# Counter_PickUp_v2.net
KiCad netlist of a schematic drawn in Altium Designer
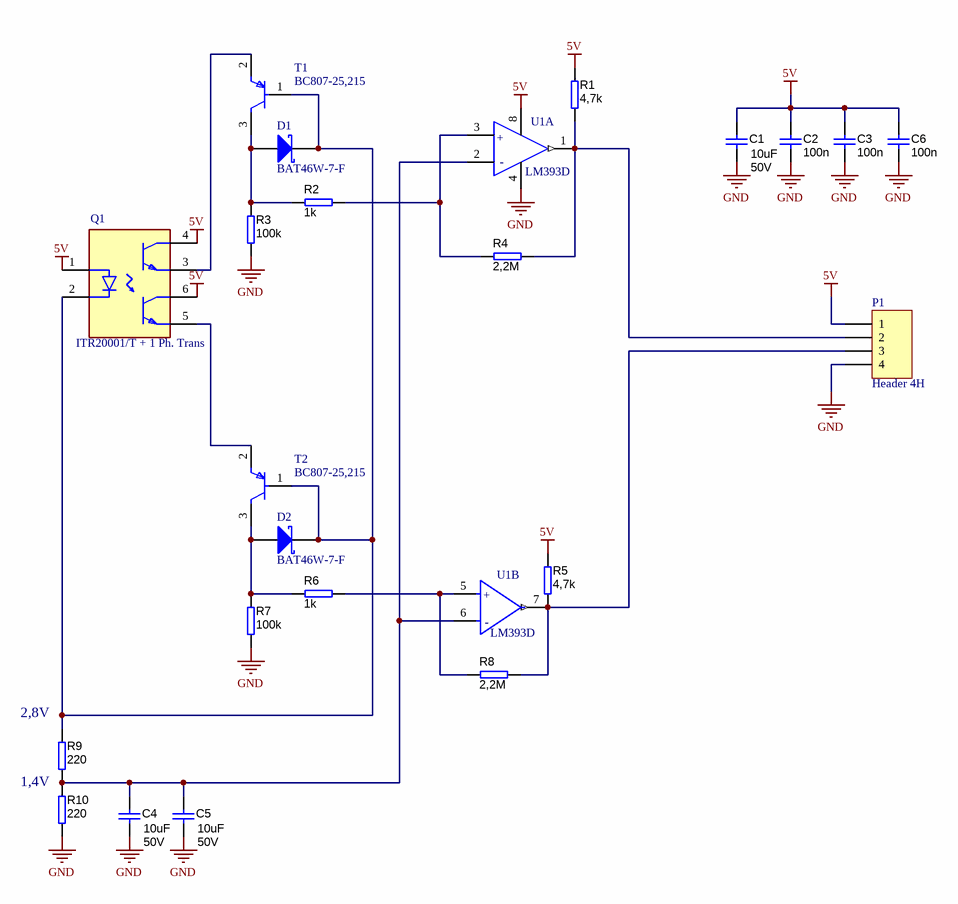
[diagram p0: Counter_PickUp_v2.SchDoc]

(export (version "E")
  (design (tool "Eeschema 10.0.6"))
  (components
    (comp (ref "C1")
      (value "10uF")
      (footprint "1206_180")
      (description "CAP, CERM, NP0, 1206")
      (fields (field (name "VALUE1") "50V"))
      (libsource (lib "Const_Cur_Source") (part "C1206"))
    )
    (comp (ref "C2")
      (value "100n")
      (footprint "0805_HV")
      (description "CAP, CERM, +/- 10%, X7S,  0805")
      (libsource (lib "Const_Cur_Source") (part "C0805"))
    )
    (comp (ref "C3")
      (value "100n")
      (footprint "0805_HV")
      (description "CAP, CERM, +/- 10%, X7S,  0805")
      (libsource (lib "Const_Cur_Source") (part "C0805"))
    )
    (comp (ref "C4")
      (value "10uF")
      (footprint "1206_180")
      (description "CAP, CERM, NP0, 1206")
      (fields (field (name "VALUE1") "50V"))
      (libsource (lib "Const_Cur_Source") (part "C1206"))
    )
    (comp (ref "C5")
      (value "10uF")
      (footprint "1206_180")
      (description "CAP, CERM, NP0, 1206")
      (fields (field (name "VALUE1") "50V"))
      (libsource (lib "Const_Cur_Source") (part "C1206"))
    )
    (comp (ref "C6")
      (value "100n")
      (footprint "0805_HV")
      (description "CAP, CERM, +/- 10%, X7S,  0805")
      (libsource (lib "Const_Cur_Source") (part "C0805"))
    )
    (comp (ref "D1")
      (value "BAT46W-7-F")
      (footprint "SOD-123-2_V")
      (description "Surface Mount Schottky Barrier Diode, 100 V, -55 to 125 degC, 2-Pin SOD123, RoHS, Tape and Reel")
      (fields (field (name "MANUFACTURER") "Diodes Inc"))
      (libsource (lib "Const_Cur_Source") (part "BAT46W-7-F"))
    )
    (comp (ref "D2")
      (value "BAT46W-7-F")
      (footprint "SOD-123-2_V")
      (description "Surface Mount Schottky Barrier Diode, 100 V, -55 to 125 degC, 2-Pin SOD123, RoHS, Tape and Reel")
      (fields (field (name "MANUFACTURER") "Diodes Inc"))
      (libsource (lib "Const_Cur_Source") (part "BAT46W-7-F"))
    )
    (comp (ref "P1")
      (value "Header 4H")
      (footprint "HDR1X4H")
      (description "Header, 4-Pin, Right Angle")
      (fields (field (name "PUBLISHER") "Altium Limited"))
      (libsource (lib "Miscellaneous Connectors") (part "Header 4H"))
    )
    (comp (ref "Q1")
      (value "Photo_T")
      (footprint "Photo_T")
      (libsource (lib "Const_Cur_Source") (part "Photo_T"))
    )
    (comp (ref "R1")
      (value "4,7k")
      (footprint "0805_HV")
      (description "RES, 1%, 0.1 W, 0805")
      (libsource (lib "Const_Cur_Source") (part "R0805"))
    )
    (comp (ref "R2")
      (value "1k")
      (footprint "0805_HV")
      (description "RES, 1%, 0.1 W, 0805")
      (libsource (lib "Const_Cur_Source") (part "R0805"))
    )
    (comp (ref "R3")
      (value "100k")
      (footprint "0805_HV")
      (description "RES, 1%, 0.1 W, 0805")
      (libsource (lib "Const_Cur_Source") (part "R0805"))
    )
    (comp (ref "R4")
      (value "2,2M")
      (footprint "0805_HV")
      (description "RES, 1%, 0.1 W, 0805")
      (libsource (lib "Const_Cur_Source") (part "R0805"))
    )
    (comp (ref "R5")
      (value "4,7k")
      (footprint "0805_HV")
      (description "RES, 1%, 0.1 W, 0805")
      (libsource (lib "Const_Cur_Source") (part "R0805"))
    )
    (comp (ref "R6")
      (value "1k")
      (footprint "0805_HV")
      (description "RES, 1%, 0.1 W, 0805")
      (libsource (lib "Const_Cur_Source") (part "R0805"))
    )
    (comp (ref "R7")
      (value "100k")
      (footprint "0805_HV")
      (description "RES, 1%, 0.1 W, 0805")
      (libsource (lib "Const_Cur_Source") (part "R0805"))
    )
    (comp (ref "R8")
      (value "2,2M")
      (footprint "0805_HV")
      (description "RES, 1%, 0.1 W, 0805")
      (libsource (lib "Const_Cur_Source") (part "R0805"))
    )
    (comp (ref "R9")
      (value "220")
      (footprint "0805_HV")
      (description "RES, 1%, 0.1 W, 0805")
      (libsource (lib "Const_Cur_Source") (part "R0805"))
    )
    (comp (ref "R10")
      (value "220")
      (footprint "0805_HV")
      (description "RES, 1%, 0.1 W, 0805")
      (libsource (lib "Const_Cur_Source") (part "R0805"))
    )
    (comp (ref "T1")
      (value "BC807-25,215")
      (footprint "SOT23_0")
      (libsource (lib "Const_Cur_Source") (part "BC807-25,215"))
    )
    (comp (ref "T2")
      (value "BC807-25,215")
      (footprint "SOT23_0")
      (libsource (lib "Const_Cur_Source") (part "BC807-25,215"))
    )
    (comp (ref "U1")
      (value "LM393D")
      (footprint "SO8_IPC_A")
      (libsource (lib "Const_Cur_Source") (part "LM393D"))
    )
  )
  (nets
    (net (code "1") (name "5V") (class "Default")
      (node (ref "C1") (pin "1") (pinfunction "1_1") (pintype "passive"))
      (node (ref "C2") (pin "2") (pinfunction "2_2") (pintype "passive"))
      (node (ref "C3") (pin "2") (pinfunction "2_2") (pintype "passive"))
      (node (ref "C6") (pin "2") (pinfunction "2_2") (pintype "passive"))
      (node (ref "P1") (pin "1") (pinfunction "1_1") (pintype "passive"))
      (node (ref "Q1") (pin "1") (pinfunction "1_ANODE_1") (pintype "passive"))
      (node (ref "Q1") (pin "4") (pinfunction "C_4") (pintype "passive"))
      (node (ref "Q1") (pin "6") (pinfunction "C_6") (pintype "passive"))
      (node (ref "R1") (pin "1") (pinfunction "1_1") (pintype "passive"))
      (node (ref "R5") (pin "1") (pinfunction "1_1") (pintype "passive"))
      (node (ref "U1") (pin "8") (pinfunction "Vcc+_8") (pintype "power_in"))
    )
    (net (code "2") (name "GND") (class "Default")
      (node (ref "C1") (pin "2") (pinfunction "2_2") (pintype "passive"))
      (node (ref "C2") (pin "1") (pinfunction "1_1") (pintype "passive"))
      (node (ref "C3") (pin "1") (pinfunction "1_1") (pintype "passive"))
      (node (ref "C4") (pin "2") (pinfunction "2_2") (pintype "passive"))
      (node (ref "C5") (pin "2") (pinfunction "2_2") (pintype "passive"))
      (node (ref "C6") (pin "1") (pinfunction "1_1") (pintype "passive"))
      (node (ref "P1") (pin "4") (pinfunction "4_4") (pintype "passive"))
      (node (ref "R10") (pin "1") (pinfunction "1_1") (pintype "passive"))
      (node (ref "R3") (pin "2") (pinfunction "2_2") (pintype "passive"))
      (node (ref "R7") (pin "2") (pinfunction "2_2") (pintype "passive"))
      (node (ref "U1") (pin "4") (pinfunction "Vcc-_4") (pintype "power_in"))
    )
    (net (code "3") (name "Net-(D1-A)") (class "Default")
      (node (ref "D1") (pin "1") (pinfunction "A_1") (pintype "passive"))
      (node (ref "R2") (pin "1") (pinfunction "1_1") (pintype "passive"))
      (node (ref "R3") (pin "1") (pinfunction "1_1") (pintype "passive"))
      (node (ref "T1") (pin "3") (pinfunction "C_3") (pintype "passive"))
    )
    (net (code "4") (name "Net-(D1-K)") (class "Default")
      (node (ref "D1") (pin "2") (pinfunction "K_2") (pintype "passive"))
      (node (ref "D2") (pin "2") (pinfunction "K_2") (pintype "passive"))
      (node (ref "Q1") (pin "2") (pinfunction "1_CATHODE_2") (pintype "passive"))
      (node (ref "R9") (pin "2") (pinfunction "2_2") (pintype "passive"))
      (node (ref "T1") (pin "1") (pinfunction "B_1") (pintype "passive"))
      (node (ref "T2") (pin "1") (pinfunction "B_1") (pintype "passive"))
    )
    (net (code "5") (name "Net-(D2-A)") (class "Default")
      (node (ref "D2") (pin "1") (pinfunction "A_1") (pintype "passive"))
      (node (ref "R6") (pin "1") (pinfunction "1_1") (pintype "passive"))
      (node (ref "R7") (pin "1") (pinfunction "1_1") (pintype "passive"))
      (node (ref "T2") (pin "3") (pinfunction "C_3") (pintype "passive"))
    )
    (net (code "6") (name "Net-(T1-E)") (class "Default")
      (node (ref "Q1") (pin "3") (pinfunction "E_3") (pintype "passive"))
      (node (ref "T1") (pin "2") (pinfunction "E_2") (pintype "passive"))
    )
    (net (code "7") (name "Net-(T2-E)") (class "Default")
      (node (ref "Q1") (pin "5") (pinfunction "E_5") (pintype "passive"))
      (node (ref "T2") (pin "2") (pinfunction "E_2") (pintype "passive"))
    )
    (net (code "8") (name "Net-(U1A-In1+)") (class "Default")
      (node (ref "R2") (pin "2") (pinfunction "2_2") (pintype "passive"))
      (node (ref "R4") (pin "2") (pinfunction "2_2") (pintype "passive"))
      (node (ref "U1") (pin "3") (pinfunction "In1+_3") (pintype "tri_state"))
    )
    (net (code "9") (name "Net-(U1A-In1-)") (class "Default")
      (node (ref "C4") (pin "1") (pinfunction "1_1") (pintype "passive"))
      (node (ref "C5") (pin "1") (pinfunction "1_1") (pintype "passive"))
      (node (ref "R10") (pin "2") (pinfunction "2_2") (pintype "passive"))
      (node (ref "R9") (pin "1") (pinfunction "1_1") (pintype "passive"))
      (node (ref "U1") (pin "2") (pinfunction "In1-_2") (pintype "tri_state"))
      (node (ref "U1") (pin "6") (pinfunction "In2-_6") (pintype "tri_state"))
    )
    (net (code "10") (name "Net-(U1A-Out1)") (class "Default")
      (node (ref "P1") (pin "2") (pinfunction "2_2") (pintype "passive"))
      (node (ref "R1") (pin "2") (pinfunction "2_2") (pintype "passive"))
      (node (ref "R4") (pin "1") (pinfunction "1_1") (pintype "passive"))
      (node (ref "U1") (pin "1") (pinfunction "Out1_1") (pintype "output"))
    )
    (net (code "11") (name "Net-(U1B-In2+)") (class "Default")
      (node (ref "R6") (pin "2") (pinfunction "2_2") (pintype "passive"))
      (node (ref "R8") (pin "2") (pinfunction "2_2") (pintype "passive"))
      (node (ref "U1") (pin "5") (pinfunction "In2+_5") (pintype "tri_state"))
    )
    (net (code "12") (name "Net-(U1B-Out2)") (class "Default")
      (node (ref "P1") (pin "3") (pinfunction "3_3") (pintype "passive"))
      (node (ref "R5") (pin "2") (pinfunction "2_2") (pintype "passive"))
      (node (ref "R8") (pin "1") (pinfunction "1_1") (pintype "passive"))
      (node (ref "U1") (pin "7") (pinfunction "Out2_7") (pintype "output"))
    )
  )
)
